# schematic.net
KiCad netlist of a schematic drawn in Altium Designer
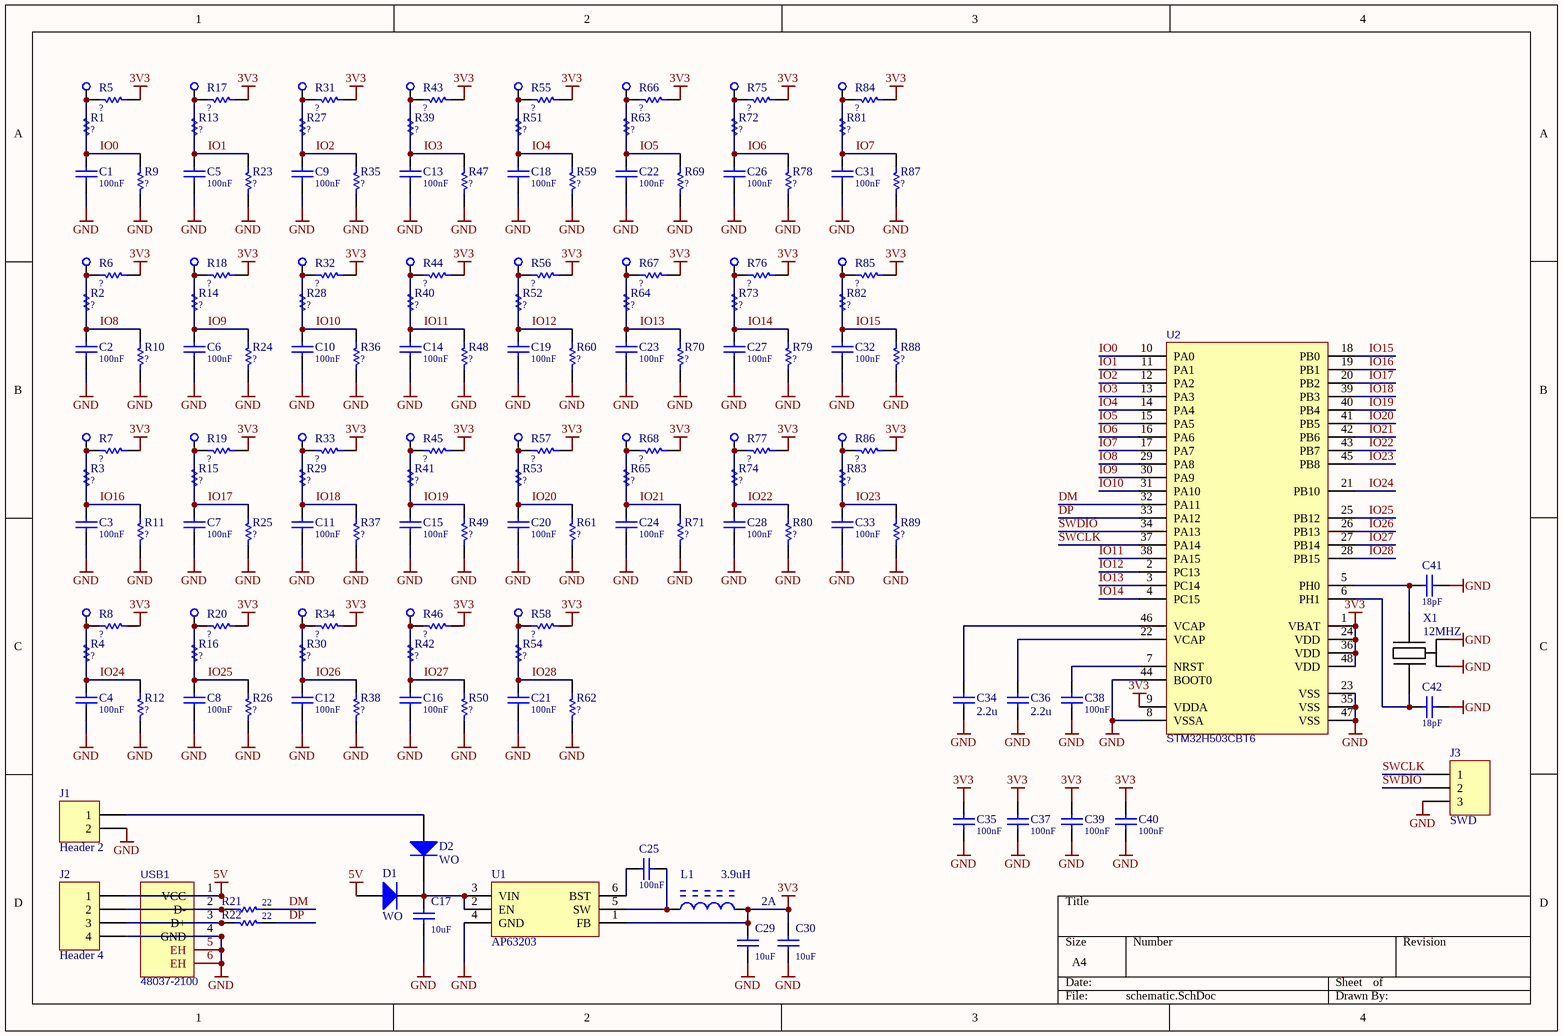
[diagram p0: schematic.SchDoc]

(export (version "E")
  (design (tool "Eeschema 10.0.6"))
  (components
    (comp (ref "C1")
      (value "100nF")
      (footprint "C0603")
      (description "100nF 0603")
      (libsource (lib "Miscellaneous Devices") (part "CAP"))
    )
    (comp (ref "C2")
      (value "100nF")
      (footprint "C0603")
      (description "100nF 0603")
      (libsource (lib "Miscellaneous Devices") (part "CAP"))
    )
    (comp (ref "C3")
      (value "100nF")
      (footprint "C0603")
      (description "100nF 0603")
      (libsource (lib "Miscellaneous Devices") (part "CAP"))
    )
    (comp (ref "C4")
      (value "100nF")
      (footprint "C0603")
      (description "100nF 0603")
      (libsource (lib "Miscellaneous Devices") (part "CAP"))
    )
    (comp (ref "C5")
      (value "100nF")
      (footprint "C0603")
      (description "100nF 0603")
      (libsource (lib "Miscellaneous Devices") (part "CAP"))
    )
    (comp (ref "C6")
      (value "100nF")
      (footprint "C0603")
      (description "100nF 0603")
      (libsource (lib "Miscellaneous Devices") (part "CAP"))
    )
    (comp (ref "C7")
      (value "100nF")
      (footprint "C0603")
      (description "100nF 0603")
      (libsource (lib "Miscellaneous Devices") (part "CAP"))
    )
    (comp (ref "C8")
      (value "100nF")
      (footprint "C0603")
      (description "100nF 0603")
      (libsource (lib "Miscellaneous Devices") (part "CAP"))
    )
    (comp (ref "C9")
      (value "100nF")
      (footprint "C0603")
      (description "100nF 0603")
      (libsource (lib "Miscellaneous Devices") (part "CAP"))
    )
    (comp (ref "C10")
      (value "100nF")
      (footprint "C0603")
      (description "100nF 0603")
      (libsource (lib "Miscellaneous Devices") (part "CAP"))
    )
    (comp (ref "C11")
      (value "100nF")
      (footprint "C0603")
      (description "100nF 0603")
      (libsource (lib "Miscellaneous Devices") (part "CAP"))
    )
    (comp (ref "C12")
      (value "100nF")
      (footprint "C0603")
      (description "100nF 0603")
      (libsource (lib "Miscellaneous Devices") (part "CAP"))
    )
    (comp (ref "C13")
      (value "100nF")
      (footprint "C0603")
      (description "100nF 0603")
      (libsource (lib "Miscellaneous Devices") (part "CAP"))
    )
    (comp (ref "C14")
      (value "100nF")
      (footprint "C0603")
      (description "100nF 0603")
      (libsource (lib "Miscellaneous Devices") (part "CAP"))
    )
    (comp (ref "C15")
      (value "100nF")
      (footprint "C0603")
      (description "100nF 0603")
      (libsource (lib "Miscellaneous Devices") (part "CAP"))
    )
    (comp (ref "C16")
      (value "100nF")
      (footprint "C0603")
      (description "100nF 0603")
      (libsource (lib "Miscellaneous Devices") (part "CAP"))
    )
    (comp (ref "C17")
      (value "10uF")
      (footprint "C1206")
      (description "10uf 50V 1206")
      (fields (field (name "LCSC PART NUMBER") "C89632"))
      (libsource (lib "Miscellaneous Devices") (part "CAP"))
    )
    (comp (ref "C18")
      (value "100nF")
      (footprint "C0603")
      (description "100nF 0603")
      (libsource (lib "Miscellaneous Devices") (part "CAP"))
    )
    (comp (ref "C19")
      (value "100nF")
      (footprint "C0603")
      (description "100nF 0603")
      (libsource (lib "Miscellaneous Devices") (part "CAP"))
    )
    (comp (ref "C20")
      (value "100nF")
      (footprint "C0603")
      (description "100nF 0603")
      (libsource (lib "Miscellaneous Devices") (part "CAP"))
    )
    (comp (ref "C21")
      (value "100nF")
      (footprint "C0603")
      (description "100nF 0603")
      (libsource (lib "Miscellaneous Devices") (part "CAP"))
    )
    (comp (ref "C22")
      (value "100nF")
      (footprint "C0603")
      (description "100nF 0603")
      (libsource (lib "Miscellaneous Devices") (part "CAP"))
    )
    (comp (ref "C23")
      (value "100nF")
      (footprint "C0603")
      (description "100nF 0603")
      (libsource (lib "Miscellaneous Devices") (part "CAP"))
    )
    (comp (ref "C24")
      (value "100nF")
      (footprint "C0603")
      (description "100nF 0603")
      (libsource (lib "Miscellaneous Devices") (part "CAP"))
    )
    (comp (ref "C25")
      (value "100nF")
      (footprint "C0402")
      (description "100nF 0402")
      (fields (field (name "LCSC PART NUMBER") "C131394"))
      (libsource (lib "Miscellaneous Devices") (part "CAP"))
    )
    (comp (ref "C26")
      (value "100nF")
      (footprint "C0603")
      (description "100nF 0603")
      (libsource (lib "Miscellaneous Devices") (part "CAP"))
    )
    (comp (ref "C27")
      (value "100nF")
      (footprint "C0603")
      (description "100nF 0603")
      (libsource (lib "Miscellaneous Devices") (part "CAP"))
    )
    (comp (ref "C28")
      (value "100nF")
      (footprint "C0603")
      (description "100nF 0603")
      (libsource (lib "Miscellaneous Devices") (part "CAP"))
    )
    (comp (ref "C29")
      (value "10uF")
      (footprint "C1206")
      (description "10uf 50V 1206")
      (fields (field (name "LCSC PART NUMBER") "C89632"))
      (libsource (lib "Miscellaneous Devices") (part "CAP"))
    )
    (comp (ref "C30")
      (value "10uF")
      (footprint "C1206")
      (description "10uf 50V 1206")
      (fields (field (name "LCSC PART NUMBER") "C89632"))
      (libsource (lib "Miscellaneous Devices") (part "CAP"))
    )
    (comp (ref "C31")
      (value "100nF")
      (footprint "C0603")
      (description "100nF 0603")
      (libsource (lib "Miscellaneous Devices") (part "CAP"))
    )
    (comp (ref "C32")
      (value "100nF")
      (footprint "C0603")
      (description "100nF 0603")
      (libsource (lib "Miscellaneous Devices") (part "CAP"))
    )
    (comp (ref "C33")
      (value "100nF")
      (footprint "C0603")
      (description "100nF 0603")
      (libsource (lib "Miscellaneous Devices") (part "CAP"))
    )
    (comp (ref "C34")
      (value "2.2u")
      (footprint "C0603")
      (libsource (lib "Miscellaneous Devices") (part "Cap"))
    )
    (comp (ref "C35")
      (value "100nF")
      (footprint "C0402")
      (libsource (lib "Miscellaneous Devices") (part "CAP"))
    )
    (comp (ref "C36")
      (value "2.2u")
      (footprint "C0603")
      (libsource (lib "Miscellaneous Devices") (part "Cap"))
    )
    (comp (ref "C37")
      (value "100nF")
      (footprint "C0402")
      (libsource (lib "Miscellaneous Devices") (part "CAP"))
    )
    (comp (ref "C38")
      (value "100nF")
      (footprint "C0402")
      (libsource (lib "Miscellaneous Devices") (part "CAP"))
    )
    (comp (ref "C39")
      (value "100nF")
      (footprint "C0402")
      (libsource (lib "Miscellaneous Devices") (part "CAP"))
    )
    (comp (ref "C40")
      (value "100nF")
      (footprint "C0402")
      (libsource (lib "Miscellaneous Devices") (part "CAP"))
    )
    (comp (ref "C41")
      (value "18pF")
      (footprint "C0402")
      (description "18pF 50V 0402")
      (fields (field (name "LCSC PART NUMBER") "C33149"))
      (libsource (lib "Miscellaneous Devices") (part "CAP"))
    )
    (comp (ref "C42")
      (value "18pF")
      (footprint "C0402")
      (description "18pF 50V 0402")
      (fields (field (name "LCSC PART NUMBER") "C33149"))
      (libsource (lib "Miscellaneous Devices") (part "CAP"))
    )
    (comp (ref "D1")
      (value "WO")
      (footprint "SMA")
      (libsource (lib "Miscellaneous Devices") (part "US1M-13-F"))
    )
    (comp (ref "D2")
      (value "WO")
      (footprint "SMA")
      (libsource (lib "Miscellaneous Devices") (part "US1M-13-F"))
    )
    (comp (ref "DN1")
      (value "~")
      (footprint "PAD_CAST2_0.8MM")
      (libsource (lib "Schlib1") (part "dummy net"))
    )
    (comp (ref "DN2")
      (value "~")
      (footprint "PAD_CAST2_0.8MM")
      (libsource (lib "Schlib1") (part "dummy net"))
    )
    (comp (ref "DN3")
      (value "~")
      (footprint "PAD_CAST2_0.8MM")
      (libsource (lib "Schlib1") (part "dummy net"))
    )
    (comp (ref "DN4")
      (value "~")
      (footprint "PAD_CAST2_0.8MM")
      (libsource (lib "Schlib1") (part "dummy net"))
    )
    (comp (ref "DN5")
      (value "~")
      (footprint "PAD_CAST2_0.8MM")
      (libsource (lib "Schlib1") (part "dummy net"))
    )
    (comp (ref "DN6")
      (value "~")
      (footprint "PAD_CAST2_0.8MM")
      (libsource (lib "Schlib1") (part "dummy net"))
    )
    (comp (ref "DN7")
      (value "~")
      (footprint "PAD_CAST2_0.8MM")
      (libsource (lib "Schlib1") (part "dummy net"))
    )
    (comp (ref "DN8")
      (value "~")
      (footprint "PAD_CAST2_0.8MM")
      (libsource (lib "Schlib1") (part "dummy net"))
    )
    (comp (ref "DN9")
      (value "~")
      (footprint "PAD_CAST2_0.8MM")
      (libsource (lib "Schlib1") (part "dummy net"))
    )
    (comp (ref "DN10")
      (value "~")
      (footprint "PAD_CAST2_0.8MM")
      (libsource (lib "Schlib1") (part "dummy net"))
    )
    (comp (ref "DN11")
      (value "~")
      (footprint "PAD_CAST2_0.8MM")
      (libsource (lib "Schlib1") (part "dummy net"))
    )
    (comp (ref "DN12")
      (value "~")
      (footprint "PAD_CAST2_0.8MM")
      (libsource (lib "Schlib1") (part "dummy net"))
    )
    (comp (ref "DN13")
      (value "~")
      (footprint "PAD_CAST2_0.8MM")
      (libsource (lib "Schlib1") (part "dummy net"))
    )
    (comp (ref "DN14")
      (value "~")
      (footprint "PAD_CAST2_0.8MM")
      (libsource (lib "Schlib1") (part "dummy net"))
    )
    (comp (ref "DN15")
      (value "~")
      (footprint "PAD_CAST2_0.8MM")
      (libsource (lib "Schlib1") (part "dummy net"))
    )
    (comp (ref "DN16")
      (value "~")
      (footprint "PAD_CAST2_0.8MM")
      (libsource (lib "Schlib1") (part "dummy net"))
    )
    (comp (ref "DN17")
      (value "~")
      (footprint "PAD_CAST2_0.8MM")
      (libsource (lib "Schlib1") (part "dummy net"))
    )
    (comp (ref "DN18")
      (value "~")
      (footprint "PAD_CAST2_0.8MM")
      (libsource (lib "Schlib1") (part "dummy net"))
    )
    (comp (ref "DN19")
      (value "~")
      (footprint "PAD_CAST2_0.8MM")
      (libsource (lib "Schlib1") (part "dummy net"))
    )
    (comp (ref "DN20")
      (value "~")
      (footprint "PAD_CAST2_0.8MM")
      (libsource (lib "Schlib1") (part "dummy net"))
    )
    (comp (ref "DN21")
      (value "~")
      (footprint "PAD_CAST2_0.8MM")
      (libsource (lib "Schlib1") (part "dummy net"))
    )
    (comp (ref "DN22")
      (value "~")
      (footprint "PAD_CAST2_0.8MM")
      (libsource (lib "Schlib1") (part "dummy net"))
    )
    (comp (ref "DN23")
      (value "~")
      (footprint "PAD_CAST2_0.8MM")
      (libsource (lib "Schlib1") (part "dummy net"))
    )
    (comp (ref "DN24")
      (value "~")
      (footprint "PAD_CAST2_0.8MM")
      (libsource (lib "Schlib1") (part "dummy net"))
    )
    (comp (ref "DN25")
      (value "~")
      (footprint "PAD_CAST2_0.8MM")
      (libsource (lib "Schlib1") (part "dummy net"))
    )
    (comp (ref "DN26")
      (value "~")
      (footprint "PAD_CAST2_0.8MM")
      (libsource (lib "Schlib1") (part "dummy net"))
    )
    (comp (ref "DN27")
      (value "~")
      (footprint "PAD_CAST2_0.8MM")
      (libsource (lib "Schlib1") (part "dummy net"))
    )
    (comp (ref "DN28")
      (value "~")
      (footprint "PAD_CAST2_0.8MM")
      (libsource (lib "Schlib1") (part "dummy net"))
    )
    (comp (ref "DN29")
      (value "~")
      (footprint "PAD_CAST2_0.8MM")
      (libsource (lib "Schlib1") (part "dummy net"))
    )
    (comp (ref "J1")
      (value "Header 2")
      (footprint "HDR-1X2_2.54")
      (libsource (lib "Schlib1") (part "Header 2"))
    )
    (comp (ref "J2")
      (value "Header 4")
      (footprint "HDR-1X4_2.54")
      (libsource (lib "Schlib1") (part "Header 4"))
    )
    (comp (ref "J3")
      (value "SWD")
      (footprint "HDR-1X3_2.54")
      (libsource (lib "Miscellaneous Devices") (part "Header 3"))
    )
    (comp (ref "L1")
      (value "3.9uH")
      (footprint "IND_5020_L5.0-W5.0")
      (description "3.9uH 2A")
      (fields (field (name "LCSC PART NUMBER") "C115009"))
      (libsource (lib "Miscellaneous Devices") (part "SRN3015-100M"))
    )
    (comp (ref "R1") (value "?") (footprint "R0603") (libsource (lib "Miscellaneous Devices") (part "RES")))
    (comp (ref "R2") (value "?") (footprint "R0603") (libsource (lib "Miscellaneous Devices") (part "RES")))
    (comp (ref "R3") (value "?") (footprint "R0603") (libsource (lib "Miscellaneous Devices") (part "RES")))
    (comp (ref "R4") (value "?") (footprint "R0603") (libsource (lib "Miscellaneous Devices") (part "RES")))
    (comp (ref "R5") (value "?") (footprint "R0603") (libsource (lib "Miscellaneous Devices") (part "RES")))
    (comp (ref "R6") (value "?") (footprint "R0603") (libsource (lib "Miscellaneous Devices") (part "RES")))
    (comp (ref "R7") (value "?") (footprint "R0603") (libsource (lib "Miscellaneous Devices") (part "RES")))
    (comp (ref "R8") (value "?") (footprint "R0603") (libsource (lib "Miscellaneous Devices") (part "RES")))
    (comp (ref "R9") (value "?") (footprint "R0603") (libsource (lib "Miscellaneous Devices") (part "RES")))
    (comp (ref "R10") (value "?") (footprint "R0603") (libsource (lib "Miscellaneous Devices") (part "RES")))
    (comp (ref "R11") (value "?") (footprint "R0603") (libsource (lib "Miscellaneous Devices") (part "RES")))
    (comp (ref "R12") (value "?") (footprint "R0603") (libsource (lib "Miscellaneous Devices") (part "RES")))
    (comp (ref "R13") (value "?") (footprint "R0603") (libsource (lib "Miscellaneous Devices") (part "RES")))
    (comp (ref "R14") (value "?") (footprint "R0603") (libsource (lib "Miscellaneous Devices") (part "RES")))
    (comp (ref "R15") (value "?") (footprint "R0603") (libsource (lib "Miscellaneous Devices") (part "RES")))
    (comp (ref "R16") (value "?") (footprint "R0603") (libsource (lib "Miscellaneous Devices") (part "RES")))
    (comp (ref "R17") (value "?") (footprint "R0603") (libsource (lib "Miscellaneous Devices") (part "RES")))
    (comp (ref "R18") (value "?") (footprint "R0603") (libsource (lib "Miscellaneous Devices") (part "RES")))
    (comp (ref "R19") (value "?") (footprint "R0603") (libsource (lib "Miscellaneous Devices") (part "RES")))
    (comp (ref "R20") (value "?") (footprint "R0603") (libsource (lib "Miscellaneous Devices") (part "RES")))
    (comp (ref "R21") (value "22") (footprint "R0603") (libsource (lib "Miscellaneous Devices") (part "RES")))
    (comp (ref "R22") (value "22") (footprint "R0603") (libsource (lib "Miscellaneous Devices") (part "RES")))
    (comp (ref "R23") (value "?") (footprint "R0603") (libsource (lib "Miscellaneous Devices") (part "RES")))
    (comp (ref "R24") (value "?") (footprint "R0603") (libsource (lib "Miscellaneous Devices") (part "RES")))
    (comp (ref "R25") (value "?") (footprint "R0603") (libsource (lib "Miscellaneous Devices") (part "RES")))
    (comp (ref "R26") (value "?") (footprint "R0603") (libsource (lib "Miscellaneous Devices") (part "RES")))
    (comp (ref "R27") (value "?") (footprint "R0603") (libsource (lib "Miscellaneous Devices") (part "RES")))
    (comp (ref "R28") (value "?") (footprint "R0603") (libsource (lib "Miscellaneous Devices") (part "RES")))
    (comp (ref "R29") (value "?") (footprint "R0603") (libsource (lib "Miscellaneous Devices") (part "RES")))
    (comp (ref "R30") (value "?") (footprint "R0603") (libsource (lib "Miscellaneous Devices") (part "RES")))
    (comp (ref "R31") (value "?") (footprint "R0603") (libsource (lib "Miscellaneous Devices") (part "RES")))
    (comp (ref "R32") (value "?") (footprint "R0603") (libsource (lib "Miscellaneous Devices") (part "RES")))
    (comp (ref "R33") (value "?") (footprint "R0603") (libsource (lib "Miscellaneous Devices") (part "RES")))
    (comp (ref "R34") (value "?") (footprint "R0603") (libsource (lib "Miscellaneous Devices") (part "RES")))
    (comp (ref "R35") (value "?") (footprint "R0603") (libsource (lib "Miscellaneous Devices") (part "RES")))
    (comp (ref "R36") (value "?") (footprint "R0603") (libsource (lib "Miscellaneous Devices") (part "RES")))
    (comp (ref "R37") (value "?") (footprint "R0603") (libsource (lib "Miscellaneous Devices") (part "RES")))
    (comp (ref "R38") (value "?") (footprint "R0603") (libsource (lib "Miscellaneous Devices") (part "RES")))
    (comp (ref "R39") (value "?") (footprint "R0603") (libsource (lib "Miscellaneous Devices") (part "RES")))
    (comp (ref "R40") (value "?") (footprint "R0603") (libsource (lib "Miscellaneous Devices") (part "RES")))
    (comp (ref "R41") (value "?") (footprint "R0603") (libsource (lib "Miscellaneous Devices") (part "RES")))
    (comp (ref "R42") (value "?") (footprint "R0603") (libsource (lib "Miscellaneous Devices") (part "RES")))
    (comp (ref "R43") (value "?") (footprint "R0603") (libsource (lib "Miscellaneous Devices") (part "RES")))
    (comp (ref "R44") (value "?") (footprint "R0603") (libsource (lib "Miscellaneous Devices") (part "RES")))
    (comp (ref "R45") (value "?") (footprint "R0603") (libsource (lib "Miscellaneous Devices") (part "RES")))
    (comp (ref "R46") (value "?") (footprint "R0603") (libsource (lib "Miscellaneous Devices") (part "RES")))
    (comp (ref "R47") (value "?") (footprint "R0603") (libsource (lib "Miscellaneous Devices") (part "RES")))
    (comp (ref "R48") (value "?") (footprint "R0603") (libsource (lib "Miscellaneous Devices") (part "RES")))
    (comp (ref "R49") (value "?") (footprint "R0603") (libsource (lib "Miscellaneous Devices") (part "RES")))
    (comp (ref "R50") (value "?") (footprint "R0603") (libsource (lib "Miscellaneous Devices") (part "RES")))
    (comp (ref "R51") (value "?") (footprint "R0603") (libsource (lib "Miscellaneous Devices") (part "RES")))
    (comp (ref "R52") (value "?") (footprint "R0603") (libsource (lib "Miscellaneous Devices") (part "RES")))
    (comp (ref "R53") (value "?") (footprint "R0603") (libsource (lib "Miscellaneous Devices") (part "RES")))
    (comp (ref "R54") (value "?") (footprint "R0603") (libsource (lib "Miscellaneous Devices") (part "RES")))
    (comp (ref "R55") (value "?") (footprint "R0603") (libsource (lib "Miscellaneous Devices") (part "RES")))
    (comp (ref "R56") (value "?") (footprint "R0603") (libsource (lib "Miscellaneous Devices") (part "RES")))
    (comp (ref "R57") (value "?") (footprint "R0603") (libsource (lib "Miscellaneous Devices") (part "RES")))
    (comp (ref "R58") (value "?") (footprint "R0603") (libsource (lib "Miscellaneous Devices") (part "RES")))
    (comp (ref "R59") (value "?") (footprint "R0603") (libsource (lib "Miscellaneous Devices") (part "RES")))
    (comp (ref "R60") (value "?") (footprint "R0603") (libsource (lib "Miscellaneous Devices") (part "RES")))
    (comp (ref "R61") (value "?") (footprint "R0603") (libsource (lib "Miscellaneous Devices") (part "RES")))
    (comp (ref "R62") (value "?") (footprint "R0603") (libsource (lib "Miscellaneous Devices") (part "RES")))
    (comp (ref "R63") (value "?") (footprint "R0603") (libsource (lib "Miscellaneous Devices") (part "RES")))
    (comp (ref "R64") (value "?") (footprint "R0603") (libsource (lib "Miscellaneous Devices") (part "RES")))
    (comp (ref "R65") (value "?") (footprint "R0603") (libsource (lib "Miscellaneous Devices") (part "RES")))
    (comp (ref "R66") (value "?") (footprint "R0603") (libsource (lib "Miscellaneous Devices") (part "RES")))
    (comp (ref "R67") (value "?") (footprint "R0603") (libsource (lib "Miscellaneous Devices") (part "RES")))
    (comp (ref "R68") (value "?") (footprint "R0603") (libsource (lib "Miscellaneous Devices") (part "RES")))
    (comp (ref "R69") (value "?") (footprint "R0603") (libsource (lib "Miscellaneous Devices") (part "RES")))
    (comp (ref "R70") (value "?") (footprint "R0603") (libsource (lib "Miscellaneous Devices") (part "RES")))
    (comp (ref "R71") (value "?") (footprint "R0603") (libsource (lib "Miscellaneous Devices") (part "RES")))
    (comp (ref "R72") (value "?") (footprint "R0603") (libsource (lib "Miscellaneous Devices") (part "RES")))
    (comp (ref "R73") (value "?") (footprint "R0603") (libsource (lib "Miscellaneous Devices") (part "RES")))
    (comp (ref "R74") (value "?") (footprint "R0603") (libsource (lib "Miscellaneous Devices") (part "RES")))
    (comp (ref "R75") (value "?") (footprint "R0603") (libsource (lib "Miscellaneous Devices") (part "RES")))
    (comp (ref "R76") (value "?") (footprint "R0603") (libsource (lib "Miscellaneous Devices") (part "RES")))
    (comp (ref "R77") (value "?") (footprint "R0603") (libsource (lib "Miscellaneous Devices") (part "RES")))
    (comp (ref "R78") (value "?") (footprint "R0603") (libsource (lib "Miscellaneous Devices") (part "RES")))
    (comp (ref "R79") (value "?") (footprint "R0603") (libsource (lib "Miscellaneous Devices") (part "RES")))
    (comp (ref "R80") (value "?") (footprint "R0603") (libsource (lib "Miscellaneous Devices") (part "RES")))
    (comp (ref "R81") (value "?") (footprint "R0603") (libsource (lib "Miscellaneous Devices") (part "RES")))
    (comp (ref "R82") (value "?") (footprint "R0603") (libsource (lib "Miscellaneous Devices") (part "RES")))
    (comp (ref "R83") (value "?") (footprint "R0603") (libsource (lib "Miscellaneous Devices") (part "RES")))
    (comp (ref "R84") (value "?") (footprint "R0603") (libsource (lib "Miscellaneous Devices") (part "RES")))
    (comp (ref "R85") (value "?") (footprint "R0603") (libsource (lib "Miscellaneous Devices") (part "RES")))
    (comp (ref "R86") (value "?") (footprint "R0603") (libsource (lib "Miscellaneous Devices") (part "RES")))
    (comp (ref "R87") (value "?") (footprint "R0603") (libsource (lib "Miscellaneous Devices") (part "RES")))
    (comp (ref "R88") (value "?") (footprint "R0603") (libsource (lib "Miscellaneous Devices") (part "RES")))
    (comp (ref "R89") (value "?") (footprint "R0603") (libsource (lib "Miscellaneous Devices") (part "RES")))
    (comp (ref "U1")
      (value "AP63203")
      (footprint "SOT-23-6")
      (fields (field (name "LCSC PART NUMBER") "C780769"))
      (libsource (lib "Schlib1") (part "AP63203"))
    )
    (comp (ref "U2")
      (value "STM32H503CBT6")
      (footprint "LQFP-48")
      (libsource (lib "Schlib1") (part "STM32H503CBT6"))
    )
    (comp (ref "USB1")
      (value "48037-2100")
      (footprint "USB-A-TH_480372100")
      (fields (field (name "LCSC PART NUMBER") "C136453"))
      (libsource (lib "Schlib1") (part "48037-2100"))
    )
    (comp (ref "X1")
      (value "12MHZ")
      (footprint "CRYSTAL_2.5x2.0mm")
      (description "CRYSTAL 12MHZ 10PF SMD")
      (fields (field (name "LCSC PART NUMBER") "C284155"))
      (libsource (lib "Miscellaneous Devices") (part "CRYSTAL 12MHZ 3.20mm x 2.50mm"))
    )
  )
  (nets
    (net (code "1") (name "/DM") (class "Default")
      (node (ref "R21") (pin "2") (pinfunction "2_2") (pintype "passive"))
      (node (ref "U2") (pin "32") (pinfunction "PA11_32") (pintype "passive"))
    )
    (net (code "2") (name "/DP") (class "Default")
      (node (ref "R22") (pin "2") (pinfunction "2_2") (pintype "passive"))
      (node (ref "U2") (pin "33") (pinfunction "PA12_33") (pintype "passive"))
    )
    (net (code "3") (name "/IO0") (class "Default")
      (node (ref "C1") (pin "2") (pinfunction "2_2") (pintype "passive"))
      (node (ref "DN1") (pin "1") (pinfunction "1_1") (pintype "passive"))
      (node (ref "R1") (pin "1") (pinfunction "1_1") (pintype "passive"))
      (node (ref "R1") (pin "2") (pinfunction "2_2") (pintype "passive"))
      (node (ref "R5") (pin "2") (pinfunction "2_2") (pintype "passive"))
      (node (ref "R9") (pin "2") (pinfunction "2_2") (pintype "passive"))
      (node (ref "U2") (pin "10") (pinfunction "PA0_10") (pintype "passive"))
    )
    (net (code "4") (name "/IO1") (class "Default")
      (node (ref "C5") (pin "2") (pinfunction "2_2") (pintype "passive"))
      (node (ref "DN5") (pin "1") (pinfunction "1_1") (pintype "passive"))
      (node (ref "R13") (pin "1") (pinfunction "1_1") (pintype "passive"))
      (node (ref "R13") (pin "2") (pinfunction "2_2") (pintype "passive"))
      (node (ref "R17") (pin "2") (pinfunction "2_2") (pintype "passive"))
      (node (ref "R23") (pin "2") (pinfunction "2_2") (pintype "passive"))
      (node (ref "U2") (pin "11") (pinfunction "PA1_11") (pintype "passive"))
    )
    (net (code "5") (name "/IO2") (class "Default")
      (node (ref "C9") (pin "2") (pinfunction "2_2") (pintype "passive"))
      (node (ref "DN9") (pin "1") (pinfunction "1_1") (pintype "passive"))
      (node (ref "R27") (pin "1") (pinfunction "1_1") (pintype "passive"))
      (node (ref "R27") (pin "2") (pinfunction "2_2") (pintype "passive"))
      (node (ref "R31") (pin "2") (pinfunction "2_2") (pintype "passive"))
      (node (ref "R35") (pin "2") (pinfunction "2_2") (pintype "passive"))
      (node (ref "U2") (pin "12") (pinfunction "PA2_12") (pintype "passive"))
    )
    (net (code "6") (name "/IO3") (class "Default")
      (node (ref "C13") (pin "2") (pinfunction "2_2") (pintype "passive"))
      (node (ref "DN13") (pin "1") (pinfunction "1_1") (pintype "passive"))
      (node (ref "R39") (pin "1") (pinfunction "1_1") (pintype "passive"))
      (node (ref "R39") (pin "2") (pinfunction "2_2") (pintype "passive"))
      (node (ref "R43") (pin "2") (pinfunction "2_2") (pintype "passive"))
      (node (ref "R47") (pin "2") (pinfunction "2_2") (pintype "passive"))
      (node (ref "U2") (pin "13") (pinfunction "PA3_13") (pintype "passive"))
    )
    (net (code "7") (name "/IO4") (class "Default")
      (node (ref "C18") (pin "2") (pinfunction "2_2") (pintype "passive"))
      (node (ref "DN17") (pin "1") (pinfunction "1_1") (pintype "passive"))
      (node (ref "R51") (pin "1") (pinfunction "1_1") (pintype "passive"))
      (node (ref "R51") (pin "2") (pinfunction "2_2") (pintype "passive"))
      (node (ref "R55") (pin "2") (pinfunction "2_2") (pintype "passive"))
      (node (ref "R59") (pin "2") (pinfunction "2_2") (pintype "passive"))
      (node (ref "U2") (pin "14") (pinfunction "PA4_14") (pintype "passive"))
    )
    (net (code "8") (name "/IO5") (class "Default")
      (node (ref "C22") (pin "2") (pinfunction "2_2") (pintype "passive"))
      (node (ref "DN21") (pin "1") (pinfunction "1_1") (pintype "passive"))
      (node (ref "R63") (pin "1") (pinfunction "1_1") (pintype "passive"))
      (node (ref "R63") (pin "2") (pinfunction "2_2") (pintype "passive"))
      (node (ref "R66") (pin "2") (pinfunction "2_2") (pintype "passive"))
      (node (ref "R69") (pin "2") (pinfunction "2_2") (pintype "passive"))
      (node (ref "U2") (pin "15") (pinfunction "PA5_15") (pintype "passive"))
    )
    (net (code "9") (name "/IO6") (class "Default")
      (node (ref "C26") (pin "2") (pinfunction "2_2") (pintype "passive"))
      (node (ref "DN24") (pin "1") (pinfunction "1_1") (pintype "passive"))
      (node (ref "R72") (pin "1") (pinfunction "1_1") (pintype "passive"))
      (node (ref "R72") (pin "2") (pinfunction "2_2") (pintype "passive"))
      (node (ref "R75") (pin "2") (pinfunction "2_2") (pintype "passive"))
      (node (ref "R78") (pin "2") (pinfunction "2_2") (pintype "passive"))
      (node (ref "U2") (pin "16") (pinfunction "PA6_16") (pintype "passive"))
    )
    (net (code "10") (name "/IO7") (class "Default")
      (node (ref "C31") (pin "2") (pinfunction "2_2") (pintype "passive"))
      (node (ref "DN27") (pin "1") (pinfunction "1_1") (pintype "passive"))
      (node (ref "R81") (pin "1") (pinfunction "1_1") (pintype "passive"))
      (node (ref "R81") (pin "2") (pinfunction "2_2") (pintype "passive"))
      (node (ref "R84") (pin "2") (pinfunction "2_2") (pintype "passive"))
      (node (ref "R87") (pin "2") (pinfunction "2_2") (pintype "passive"))
      (node (ref "U2") (pin "17") (pinfunction "PA7_17") (pintype "passive"))
    )
    (net (code "11") (name "/IO8") (class "Default")
      (node (ref "C2") (pin "2") (pinfunction "2_2") (pintype "passive"))
      (node (ref "DN2") (pin "1") (pinfunction "1_1") (pintype "passive"))
      (node (ref "R10") (pin "2") (pinfunction "2_2") (pintype "passive"))
      (node (ref "R2") (pin "1") (pinfunction "1_1") (pintype "passive"))
      (node (ref "R2") (pin "2") (pinfunction "2_2") (pintype "passive"))
      (node (ref "R6") (pin "2") (pinfunction "2_2") (pintype "passive"))
      (node (ref "U2") (pin "29") (pinfunction "PA8_29") (pintype "passive"))
    )
    (net (code "12") (name "/IO9") (class "Default")
      (node (ref "C6") (pin "2") (pinfunction "2_2") (pintype "passive"))
      (node (ref "DN6") (pin "1") (pinfunction "1_1") (pintype "passive"))
      (node (ref "R14") (pin "1") (pinfunction "1_1") (pintype "passive"))
      (node (ref "R14") (pin "2") (pinfunction "2_2") (pintype "passive"))
      (node (ref "R18") (pin "2") (pinfunction "2_2") (pintype "passive"))
      (node (ref "R24") (pin "2") (pinfunction "2_2") (pintype "passive"))
      (node (ref "U2") (pin "30") (pinfunction "PA9_30") (pintype "passive"))
    )
    (net (code "13") (name "/IO10") (class "Default")
      (node (ref "C10") (pin "2") (pinfunction "2_2") (pintype "passive"))
      (node (ref "DN10") (pin "1") (pinfunction "1_1") (pintype "passive"))
      (node (ref "R28") (pin "1") (pinfunction "1_1") (pintype "passive"))
      (node (ref "R28") (pin "2") (pinfunction "2_2") (pintype "passive"))
      (node (ref "R32") (pin "2") (pinfunction "2_2") (pintype "passive"))
      (node (ref "R36") (pin "2") (pinfunction "2_2") (pintype "passive"))
      (node (ref "U2") (pin "31") (pinfunction "PA10_31") (pintype "passive"))
    )
    (net (code "14") (name "/IO11") (class "Default")
      (node (ref "C14") (pin "2") (pinfunction "2_2") (pintype "passive"))
      (node (ref "DN14") (pin "1") (pinfunction "1_1") (pintype "passive"))
      (node (ref "R40") (pin "1") (pinfunction "1_1") (pintype "passive"))
      (node (ref "R40") (pin "2") (pinfunction "2_2") (pintype "passive"))
      (node (ref "R44") (pin "2") (pinfunction "2_2") (pintype "passive"))
      (node (ref "R48") (pin "2") (pinfunction "2_2") (pintype "passive"))
      (node (ref "U2") (pin "38") (pinfunction "PA15_38") (pintype "passive"))
    )
    (net (code "15") (name "/IO12") (class "Default")
      (node (ref "C19") (pin "2") (pinfunction "2_2") (pintype "passive"))
      (node (ref "DN18") (pin "1") (pinfunction "1_1") (pintype "passive"))
      (node (ref "R52") (pin "1") (pinfunction "1_1") (pintype "passive"))
      (node (ref "R52") (pin "2") (pinfunction "2_2") (pintype "passive"))
      (node (ref "R56") (pin "2") (pinfunction "2_2") (pintype "passive"))
      (node (ref "R60") (pin "2") (pinfunction "2_2") (pintype "passive"))
      (node (ref "U2") (pin "2") (pinfunction "PC13_2") (pintype "passive"))
    )
    (net (code "16") (name "/IO13") (class "Default")
      (node (ref "C23") (pin "2") (pinfunction "2_2") (pintype "passive"))
      (node (ref "DN22") (pin "1") (pinfunction "1_1") (pintype "passive"))
      (node (ref "R64") (pin "1") (pinfunction "1_1") (pintype "passive"))
      (node (ref "R64") (pin "2") (pinfunction "2_2") (pintype "passive"))
      (node (ref "R67") (pin "2") (pinfunction "2_2") (pintype "passive"))
      (node (ref "R70") (pin "2") (pinfunction "2_2") (pintype "passive"))
      (node (ref "U2") (pin "3") (pinfunction "PC14_3") (pintype "passive"))
    )
    (net (code "17") (name "/IO14") (class "Default")
      (node (ref "C27") (pin "2") (pinfunction "2_2") (pintype "passive"))
      (node (ref "DN25") (pin "1") (pinfunction "1_1") (pintype "passive"))
      (node (ref "R73") (pin "1") (pinfunction "1_1") (pintype "passive"))
      (node (ref "R73") (pin "2") (pinfunction "2_2") (pintype "passive"))
      (node (ref "R76") (pin "2") (pinfunction "2_2") (pintype "passive"))
      (node (ref "R79") (pin "2") (pinfunction "2_2") (pintype "passive"))
      (node (ref "U2") (pin "4") (pinfunction "PC15_4") (pintype "passive"))
    )
    (net (code "18") (name "/IO15") (class "Default")
      (node (ref "C32") (pin "2") (pinfunction "2_2") (pintype "passive"))
      (node (ref "DN28") (pin "1") (pinfunction "1_1") (pintype "passive"))
      (node (ref "R82") (pin "1") (pinfunction "1_1") (pintype "passive"))
      (node (ref "R82") (pin "2") (pinfunction "2_2") (pintype "passive"))
      (node (ref "R85") (pin "2") (pinfunction "2_2") (pintype "passive"))
      (node (ref "R88") (pin "2") (pinfunction "2_2") (pintype "passive"))
      (node (ref "U2") (pin "18") (pinfunction "PB0_18") (pintype "passive"))
    )
    (net (code "19") (name "/IO16") (class "Default")
      (node (ref "C3") (pin "2") (pinfunction "2_2") (pintype "passive"))
      (node (ref "DN3") (pin "1") (pinfunction "1_1") (pintype "passive"))
      (node (ref "R11") (pin "2") (pinfunction "2_2") (pintype "passive"))
      (node (ref "R3") (pin "1") (pinfunction "1_1") (pintype "passive"))
      (node (ref "R3") (pin "2") (pinfunction "2_2") (pintype "passive"))
      (node (ref "R7") (pin "2") (pinfunction "2_2") (pintype "passive"))
      (node (ref "U2") (pin "19") (pinfunction "PB1_19") (pintype "passive"))
    )
    (net (code "20") (name "/IO17") (class "Default")
      (node (ref "C7") (pin "2") (pinfunction "2_2") (pintype "passive"))
      (node (ref "DN7") (pin "1") (pinfunction "1_1") (pintype "passive"))
      (node (ref "R15") (pin "1") (pinfunction "1_1") (pintype "passive"))
      (node (ref "R15") (pin "2") (pinfunction "2_2") (pintype "passive"))
      (node (ref "R19") (pin "2") (pinfunction "2_2") (pintype "passive"))
      (node (ref "R25") (pin "2") (pinfunction "2_2") (pintype "passive"))
      (node (ref "U2") (pin "20") (pinfunction "PB2_20") (pintype "passive"))
    )
    (net (code "21") (name "/IO18") (class "Default")
      (node (ref "C11") (pin "2") (pinfunction "2_2") (pintype "passive"))
      (node (ref "DN11") (pin "1") (pinfunction "1_1") (pintype "passive"))
      (node (ref "R29") (pin "1") (pinfunction "1_1") (pintype "passive"))
      (node (ref "R29") (pin "2") (pinfunction "2_2") (pintype "passive"))
      (node (ref "R33") (pin "2") (pinfunction "2_2") (pintype "passive"))
      (node (ref "R37") (pin "2") (pinfunction "2_2") (pintype "passive"))
      (node (ref "U2") (pin "39") (pinfunction "PB3_39") (pintype "passive"))
    )
    (net (code "22") (name "/IO19") (class "Default")
      (node (ref "C15") (pin "2") (pinfunction "2_2") (pintype "passive"))
      (node (ref "DN15") (pin "1") (pinfunction "1_1") (pintype "passive"))
      (node (ref "R41") (pin "1") (pinfunction "1_1") (pintype "passive"))
      (node (ref "R41") (pin "2") (pinfunction "2_2") (pintype "passive"))
      (node (ref "R45") (pin "2") (pinfunction "2_2") (pintype "passive"))
      (node (ref "R49") (pin "2") (pinfunction "2_2") (pintype "passive"))
      (node (ref "U2") (pin "40") (pinfunction "PB4_40") (pintype "passive"))
    )
    (net (code "23") (name "/IO20") (class "Default")
      (node (ref "C20") (pin "2") (pinfunction "2_2") (pintype "passive"))
      (node (ref "DN19") (pin "1") (pinfunction "1_1") (pintype "passive"))
      (node (ref "R53") (pin "1") (pinfunction "1_1") (pintype "passive"))
      (node (ref "R53") (pin "2") (pinfunction "2_2") (pintype "passive"))
      (node (ref "R57") (pin "2") (pinfunction "2_2") (pintype "passive"))
      (node (ref "R61") (pin "2") (pinfunction "2_2") (pintype "passive"))
      (node (ref "U2") (pin "41") (pinfunction "PB5_41") (pintype "passive"))
    )
    (net (code "24") (name "/IO21") (class "Default")
      (node (ref "C24") (pin "2") (pinfunction "2_2") (pintype "passive"))
      (node (ref "DN23") (pin "1") (pinfunction "1_1") (pintype "passive"))
      (node (ref "R65") (pin "1") (pinfunction "1_1") (pintype "passive"))
      (node (ref "R65") (pin "2") (pinfunction "2_2") (pintype "passive"))
      (node (ref "R68") (pin "2") (pinfunction "2_2") (pintype "passive"))
      (node (ref "R71") (pin "2") (pinfunction "2_2") (pintype "passive"))
      (node (ref "U2") (pin "42") (pinfunction "PB6_42") (pintype "passive"))
    )
    (net (code "25") (name "/IO22") (class "Default")
      (node (ref "C28") (pin "2") (pinfunction "2_2") (pintype "passive"))
      (node (ref "DN26") (pin "1") (pinfunction "1_1") (pintype "passive"))
      (node (ref "R74") (pin "1") (pinfunction "1_1") (pintype "passive"))
      (node (ref "R74") (pin "2") (pinfunction "2_2") (pintype "passive"))
      (node (ref "R77") (pin "2") (pinfunction "2_2") (pintype "passive"))
      (node (ref "R80") (pin "2") (pinfunction "2_2") (pintype "passive"))
      (node (ref "U2") (pin "43") (pinfunction "PB7_43") (pintype "passive"))
    )
    (net (code "26") (name "/IO23") (class "Default")
      (node (ref "C33") (pin "2") (pinfunction "2_2") (pintype "passive"))
      (node (ref "DN29") (pin "1") (pinfunction "1_1") (pintype "passive"))
      (node (ref "R83") (pin "1") (pinfunction "1_1") (pintype "passive"))
      (node (ref "R83") (pin "2") (pinfunction "2_2") (pintype "passive"))
      (node (ref "R86") (pin "2") (pinfunction "2_2") (pintype "passive"))
      (node (ref "R89") (pin "2") (pinfunction "2_2") (pintype "passive"))
      (node (ref "U2") (pin "45") (pinfunction "PB8_45") (pintype "passive"))
    )
    (net (code "27") (name "/IO24") (class "Default")
      (node (ref "C4") (pin "2") (pinfunction "2_2") (pintype "passive"))
      (node (ref "DN4") (pin "1") (pinfunction "1_1") (pintype "passive"))
      (node (ref "R12") (pin "2") (pinfunction "2_2") (pintype "passive"))
      (node (ref "R4") (pin "1") (pinfunction "1_1") (pintype "passive"))
      (node (ref "R4") (pin "2") (pinfunction "2_2") (pintype "passive"))
      (node (ref "R8") (pin "2") (pinfunction "2_2") (pintype "passive"))
      (node (ref "U2") (pin "21") (pinfunction "PB10_21") (pintype "passive"))
    )
    (net (code "28") (name "/IO25") (class "Default")
      (node (ref "C8") (pin "2") (pinfunction "2_2") (pintype "passive"))
      (node (ref "DN8") (pin "1") (pinfunction "1_1") (pintype "passive"))
      (node (ref "R16") (pin "1") (pinfunction "1_1") (pintype "passive"))
      (node (ref "R16") (pin "2") (pinfunction "2_2") (pintype "passive"))
      (node (ref "R20") (pin "2") (pinfunction "2_2") (pintype "passive"))
      (node (ref "R26") (pin "2") (pinfunction "2_2") (pintype "passive"))
      (node (ref "U2") (pin "25") (pinfunction "PB12_25") (pintype "passive"))
    )
    (net (code "29") (name "/IO26") (class "Default")
      (node (ref "C12") (pin "2") (pinfunction "2_2") (pintype "passive"))
      (node (ref "DN12") (pin "1") (pinfunction "1_1") (pintype "passive"))
      (node (ref "R30") (pin "1") (pinfunction "1_1") (pintype "passive"))
      (node (ref "R30") (pin "2") (pinfunction "2_2") (pintype "passive"))
      (node (ref "R34") (pin "2") (pinfunction "2_2") (pintype "passive"))
      (node (ref "R38") (pin "2") (pinfunction "2_2") (pintype "passive"))
      (node (ref "U2") (pin "26") (pinfunction "PB13_26") (pintype "passive"))
    )
    (net (code "30") (name "/IO27") (class "Default")
      (node (ref "C16") (pin "2") (pinfunction "2_2") (pintype "passive"))
      (node (ref "DN16") (pin "1") (pinfunction "1_1") (pintype "passive"))
      (node (ref "R42") (pin "1") (pinfunction "1_1") (pintype "passive"))
      (node (ref "R42") (pin "2") (pinfunction "2_2") (pintype "passive"))
      (node (ref "R46") (pin "2") (pinfunction "2_2") (pintype "passive"))
      (node (ref "R50") (pin "2") (pinfunction "2_2") (pintype "passive"))
      (node (ref "U2") (pin "27") (pinfunction "PB14_27") (pintype "passive"))
    )
    (net (code "31") (name "/IO28") (class "Default")
      (node (ref "C21") (pin "2") (pinfunction "2_2") (pintype "passive"))
      (node (ref "DN20") (pin "1") (pinfunction "1_1") (pintype "passive"))
      (node (ref "R54") (pin "1") (pinfunction "1_1") (pintype "passive"))
      (node (ref "R54") (pin "2") (pinfunction "2_2") (pintype "passive"))
      (node (ref "R58") (pin "2") (pinfunction "2_2") (pintype "passive"))
      (node (ref "R62") (pin "2") (pinfunction "2_2") (pintype "passive"))
      (node (ref "U2") (pin "28") (pinfunction "PB15_28") (pintype "passive"))
    )
    (net (code "32") (name "/SWCLK") (class "Default")
      (node (ref "J3") (pin "1") (pinfunction "1_1") (pintype "passive"))
      (node (ref "U2") (pin "37") (pinfunction "PA14_37") (pintype "passive"))
    )
    (net (code "33") (name "/SWDIO") (class "Default")
      (node (ref "J3") (pin "2") (pinfunction "2_2") (pintype "passive"))
      (node (ref "U2") (pin "34") (pinfunction "PA13_34") (pintype "passive"))
    )
    (net (code "34") (name "3V3") (class "Default")
      (node (ref "C29") (pin "2") (pinfunction "2_2") (pintype "passive"))
      (node (ref "C30") (pin "2") (pinfunction "2_2") (pintype "passive"))
      (node (ref "C35") (pin "2") (pinfunction "2_2") (pintype "passive"))
      (node (ref "C37") (pin "2") (pinfunction "2_2") (pintype "passive"))
      (node (ref "C39") (pin "2") (pinfunction "2_2") (pintype "passive"))
      (node (ref "C40") (pin "2") (pinfunction "2_2") (pintype "passive"))
      (node (ref "L1") (pin "2") (pinfunction "2_2") (pintype "passive"))
      (node (ref "R17") (pin "1") (pinfunction "1_1") (pintype "passive"))
      (node (ref "R18") (pin "1") (pinfunction "1_1") (pintype "passive"))
      (node (ref "R19") (pin "1") (pinfunction "1_1") (pintype "passive"))
      (node (ref "R20") (pin "1") (pinfunction "1_1") (pintype "passive"))
      (node (ref "R31") (pin "1") (pinfunction "1_1") (pintype "passive"))
      (node (ref "R32") (pin "1") (pinfunction "1_1") (pintype "passive"))
      (node (ref "R33") (pin "1") (pinfunction "1_1") (pintype "passive"))
      (node (ref "R34") (pin "1") (pinfunction "1_1") (pintype "passive"))
      (node (ref "R43") (pin "1") (pinfunction "1_1") (pintype "passive"))
      (node (ref "R44") (pin "1") (pinfunction "1_1") (pintype "passive"))
      (node (ref "R45") (pin "1") (pinfunction "1_1") (pintype "passive"))
      (node (ref "R46") (pin "1") (pinfunction "1_1") (pintype "passive"))
      (node (ref "R5") (pin "1") (pinfunction "1_1") (pintype "passive"))
      (node (ref "R55") (pin "1") (pinfunction "1_1") (pintype "passive"))
      (node (ref "R56") (pin "1") (pinfunction "1_1") (pintype "passive"))
      (node (ref "R57") (pin "1") (pinfunction "1_1") (pintype "passive"))
      (node (ref "R58") (pin "1") (pinfunction "1_1") (pintype "passive"))
      (node (ref "R6") (pin "1") (pinfunction "1_1") (pintype "passive"))
      (node (ref "R66") (pin "1") (pinfunction "1_1") (pintype "passive"))
      (node (ref "R67") (pin "1") (pinfunction "1_1") (pintype "passive"))
      (node (ref "R68") (pin "1") (pinfunction "1_1") (pintype "passive"))
      (node (ref "R7") (pin "1") (pinfunction "1_1") (pintype "passive"))
      (node (ref "R75") (pin "1") (pinfunction "1_1") (pintype "passive"))
      (node (ref "R76") (pin "1") (pinfunction "1_1") (pintype "passive"))
      (node (ref "R77") (pin "1") (pinfunction "1_1") (pintype "passive"))
      (node (ref "R8") (pin "1") (pinfunction "1_1") (pintype "passive"))
      (node (ref "R84") (pin "1") (pinfunction "1_1") (pintype "passive"))
      (node (ref "R85") (pin "1") (pinfunction "1_1") (pintype "passive"))
      (node (ref "R86") (pin "1") (pinfunction "1_1") (pintype "passive"))
      (node (ref "U1") (pin "1") (pinfunction "FB_1") (pintype "passive"))
      (node (ref "U2") (pin "1") (pinfunction "VBAT_1") (pintype "passive"))
      (node (ref "U2") (pin "24") (pinfunction "VDD_24") (pintype "passive"))
      (node (ref "U2") (pin "36") (pinfunction "VDD_36") (pintype "passive"))
      (node (ref "U2") (pin "48") (pinfunction "VDD_48") (pintype "passive"))
      (node (ref "U2") (pin "9") (pinfunction "VDDA_9") (pintype "passive"))
    )
    (net (code "35") (name "5V") (class "Default")
      (node (ref "D1") (pin "1") (pinfunction "A_1") (pintype "passive"))
      (node (ref "J2") (pin "1") (pinfunction "1_1") (pintype "passive"))
      (node (ref "USB1") (pin "1") (pinfunction "VCC_1") (pintype "passive"))
    )
    (net (code "36") (name "GND") (class "Default")
      (node (ref "C1") (pin "1") (pinfunction "1_1") (pintype "passive"))
      (node (ref "C10") (pin "1") (pinfunction "1_1") (pintype "passive"))
      (node (ref "C11") (pin "1") (pinfunction "1_1") (pintype "passive"))
      (node (ref "C12") (pin "1") (pinfunction "1_1") (pintype "passive"))
      (node (ref "C13") (pin "1") (pinfunction "1_1") (pintype "passive"))
      (node (ref "C14") (pin "1") (pinfunction "1_1") (pintype "passive"))
      (node (ref "C15") (pin "1") (pinfunction "1_1") (pintype "passive"))
      (node (ref "C16") (pin "1") (pinfunction "1_1") (pintype "passive"))
      (node (ref "C17") (pin "1") (pinfunction "1_1") (pintype "passive"))
      (node (ref "C18") (pin "1") (pinfunction "1_1") (pintype "passive"))
      (node (ref "C19") (pin "1") (pinfunction "1_1") (pintype "passive"))
      (node (ref "C2") (pin "1") (pinfunction "1_1") (pintype "passive"))
      (node (ref "C20") (pin "1") (pinfunction "1_1") (pintype "passive"))
      (node (ref "C21") (pin "1") (pinfunction "1_1") (pintype "passive"))
      (node (ref "C22") (pin "1") (pinfunction "1_1") (pintype "passive"))
      (node (ref "C23") (pin "1") (pinfunction "1_1") (pintype "passive"))
      (node (ref "C24") (pin "1") (pinfunction "1_1") (pintype "passive"))
      (node (ref "C26") (pin "1") (pinfunction "1_1") (pintype "passive"))
      (node (ref "C27") (pin "1") (pinfunction "1_1") (pintype "passive"))
      (node (ref "C28") (pin "1") (pinfunction "1_1") (pintype "passive"))
      (node (ref "C29") (pin "1") (pinfunction "1_1") (pintype "passive"))
      (node (ref "C3") (pin "1") (pinfunction "1_1") (pintype "passive"))
      (node (ref "C30") (pin "1") (pinfunction "1_1") (pintype "passive"))
      (node (ref "C31") (pin "1") (pinfunction "1_1") (pintype "passive"))
      (node (ref "C32") (pin "1") (pinfunction "1_1") (pintype "passive"))
      (node (ref "C33") (pin "1") (pinfunction "1_1") (pintype "passive"))
      (node (ref "C34") (pin "1") (pinfunction "1_1") (pintype "passive"))
      (node (ref "C35") (pin "1") (pinfunction "1_1") (pintype "passive"))
      (node (ref "C36") (pin "1") (pinfunction "1_1") (pintype "passive"))
      (node (ref "C37") (pin "1") (pinfunction "1_1") (pintype "passive"))
      (node (ref "C38") (pin "1") (pinfunction "1_1") (pintype "passive"))
      (node (ref "C39") (pin "1") (pinfunction "1_1") (pintype "passive"))
      (node (ref "C4") (pin "1") (pinfunction "1_1") (pintype "passive"))
      (node (ref "C40") (pin "1") (pinfunction "1_1") (pintype "passive"))
      (node (ref "C41") (pin "1") (pinfunction "1_1") (pintype "passive"))
      (node (ref "C42") (pin "1") (pinfunction "1_1") (pintype "passive"))
      (node (ref "C5") (pin "1") (pinfunction "1_1") (pintype "passive"))
      (node (ref "C6") (pin "1") (pinfunction "1_1") (pintype "passive"))
      (node (ref "C7") (pin "1") (pinfunction "1_1") (pintype "passive"))
      (node (ref "C8") (pin "1") (pinfunction "1_1") (pintype "passive"))
      (node (ref "C9") (pin "1") (pinfunction "1_1") (pintype "passive"))
      (node (ref "J1") (pin "2") (pinfunction "2_2") (pintype "passive"))
      (node (ref "J2") (pin "4") (pinfunction "4_4") (pintype "passive"))
      (node (ref "J3") (pin "3") (pinfunction "3_3") (pintype "passive"))
      (node (ref "R10") (pin "1") (pinfunction "1_1") (pintype "passive"))
      (node (ref "R11") (pin "1") (pinfunction "1_1") (pintype "passive"))
      (node (ref "R12") (pin "1") (pinfunction "1_1") (pintype "passive"))
      (node (ref "R23") (pin "1") (pinfunction "1_1") (pintype "passive"))
      (node (ref "R24") (pin "1") (pinfunction "1_1") (pintype "passive"))
      (node (ref "R25") (pin "1") (pinfunction "1_1") (pintype "passive"))
      (node (ref "R26") (pin "1") (pinfunction "1_1") (pintype "passive"))
      (node (ref "R35") (pin "1") (pinfunction "1_1") (pintype "passive"))
      (node (ref "R36") (pin "1") (pinfunction "1_1") (pintype "passive"))
      (node (ref "R37") (pin "1") (pinfunction "1_1") (pintype "passive"))
      (node (ref "R38") (pin "1") (pinfunction "1_1") (pintype "passive"))
      (node (ref "R47") (pin "1") (pinfunction "1_1") (pintype "passive"))
      (node (ref "R48") (pin "1") (pinfunction "1_1") (pintype "passive"))
      (node (ref "R49") (pin "1") (pinfunction "1_1") (pintype "passive"))
      (node (ref "R50") (pin "1") (pinfunction "1_1") (pintype "passive"))
      (node (ref "R59") (pin "1") (pinfunction "1_1") (pintype "passive"))
      (node (ref "R60") (pin "1") (pinfunction "1_1") (pintype "passive"))
      (node (ref "R61") (pin "1") (pinfunction "1_1") (pintype "passive"))
      (node (ref "R62") (pin "1") (pinfunction "1_1") (pintype "passive"))
      (node (ref "R69") (pin "1") (pinfunction "1_1") (pintype "passive"))
      (node (ref "R70") (pin "1") (pinfunction "1_1") (pintype "passive"))
      (node (ref "R71") (pin "1") (pinfunction "1_1") (pintype "passive"))
      (node (ref "R78") (pin "1") (pinfunction "1_1") (pintype "passive"))
      (node (ref "R79") (pin "1") (pinfunction "1_1") (pintype "passive"))
      (node (ref "R80") (pin "1") (pinfunction "1_1") (pintype "passive"))
      (node (ref "R87") (pin "1") (pinfunction "1_1") (pintype "passive"))
      (node (ref "R88") (pin "1") (pinfunction "1_1") (pintype "passive"))
      (node (ref "R89") (pin "1") (pinfunction "1_1") (pintype "passive"))
      (node (ref "R9") (pin "1") (pinfunction "1_1") (pintype "passive"))
      (node (ref "U1") (pin "4") (pinfunction "GND_4") (pintype "passive"))
      (node (ref "U2") (pin "23") (pinfunction "VSS_23") (pintype "passive"))
      (node (ref "U2") (pin "35") (pinfunction "VSS_35") (pintype "passive"))
      (node (ref "U2") (pin "44") (pinfunction "BOOT0_44") (pintype "passive"))
      (node (ref "U2") (pin "47") (pinfunction "VSS_47") (pintype "passive"))
      (node (ref "U2") (pin "8") (pinfunction "VSSA_8") (pintype "passive"))
      (node (ref "USB1") (pin "4") (pinfunction "GND_4") (pintype "passive"))
      (node (ref "USB1") (pin "5") (pinfunction "EH_5") (pintype "passive"))
      (node (ref "USB1") (pin "6") (pinfunction "EH_6") (pintype "passive"))
      (node (ref "X1") (pin "2") (pinfunction "GND_2") (pintype "passive"))
      (node (ref "X1") (pin "4") (pinfunction "GND_4") (pintype "passive"))
    )
    (net (code "37") (name "Net-(C34-Pad2)") (class "Default")
      (node (ref "C34") (pin "2") (pinfunction "2_2") (pintype "passive"))
      (node (ref "U2") (pin "46") (pinfunction "VCAP_46") (pintype "passive"))
    )
    (net (code "38") (name "Net-(C36-Pad2)") (class "Default")
      (node (ref "C36") (pin "2") (pinfunction "2_2") (pintype "passive"))
      (node (ref "U2") (pin "22") (pinfunction "VCAP_22") (pintype "passive"))
    )
    (net (code "39") (name "Net-(D1-K)") (class "Default")
      (node (ref "C17") (pin "2") (pinfunction "2_2") (pintype "passive"))
      (node (ref "D1") (pin "2") (pinfunction "K_2") (pintype "passive"))
      (node (ref "D2") (pin "2") (pinfunction "K_2") (pintype "passive"))
      (node (ref "U1") (pin "2") (pinfunction "EN_2") (pintype "passive"))
      (node (ref "U1") (pin "3") (pinfunction "VIN_3") (pintype "passive"))
    )
    (net (code "40") (name "Net-(D2-A)") (class "Default")
      (node (ref "D2") (pin "1") (pinfunction "A_1") (pintype "passive"))
      (node (ref "J1") (pin "1") (pinfunction "1_1") (pintype "passive"))
    )
    (net (code "41") (name "Net-(U1-BST)") (class "Default")
      (node (ref "C25") (pin "2") (pinfunction "2_2") (pintype "passive"))
      (node (ref "U1") (pin "6") (pinfunction "BST_6") (pintype "passive"))
    )
    (net (code "42") (name "Net-(U1-SW)") (class "Default")
      (node (ref "C25") (pin "1") (pinfunction "1_1") (pintype "passive"))
      (node (ref "L1") (pin "1") (pinfunction "1_1") (pintype "passive"))
      (node (ref "U1") (pin "5") (pinfunction "SW_5") (pintype "passive"))
    )
    (net (code "43") (name "Net-(U2-NRST)") (class "Default")
      (node (ref "C38") (pin "2") (pinfunction "2_2") (pintype "passive"))
      (node (ref "U2") (pin "7") (pinfunction "NRST_7") (pintype "passive"))
    )
    (net (code "44") (name "Net-(U2-PH0)") (class "Default")
      (node (ref "C41") (pin "2") (pinfunction "2_2") (pintype "passive"))
      (node (ref "U2") (pin "5") (pinfunction "PH0_5") (pintype "passive"))
      (node (ref "X1") (pin "3") (pinfunction "X2_3") (pintype "passive"))
    )
    (net (code "45") (name "Net-(U2-PH1)") (class "Default")
      (node (ref "C42") (pin "2") (pinfunction "2_2") (pintype "passive"))
      (node (ref "U2") (pin "6") (pinfunction "PH1_6") (pintype "passive"))
      (node (ref "X1") (pin "1") (pinfunction "X1_1") (pintype "passive"))
    )
    (net (code "46") (name "Net-(USB1-D+)") (class "Default")
      (node (ref "J2") (pin "3") (pinfunction "3_3") (pintype "passive"))
      (node (ref "R22") (pin "1") (pinfunction "1_1") (pintype "passive"))
      (node (ref "USB1") (pin "3") (pinfunction "D+_3") (pintype "passive"))
    )
    (net (code "47") (name "Net-(USB1-D-)") (class "Default")
      (node (ref "J2") (pin "2") (pinfunction "2_2") (pintype "passive"))
      (node (ref "R21") (pin "1") (pinfunction "1_1") (pintype "passive"))
      (node (ref "USB1") (pin "2") (pinfunction "D-_2") (pintype "passive"))
    )
  )
)
